# 1Bitsy.net
KiCad netlist of a schematic drawn in EAGLE
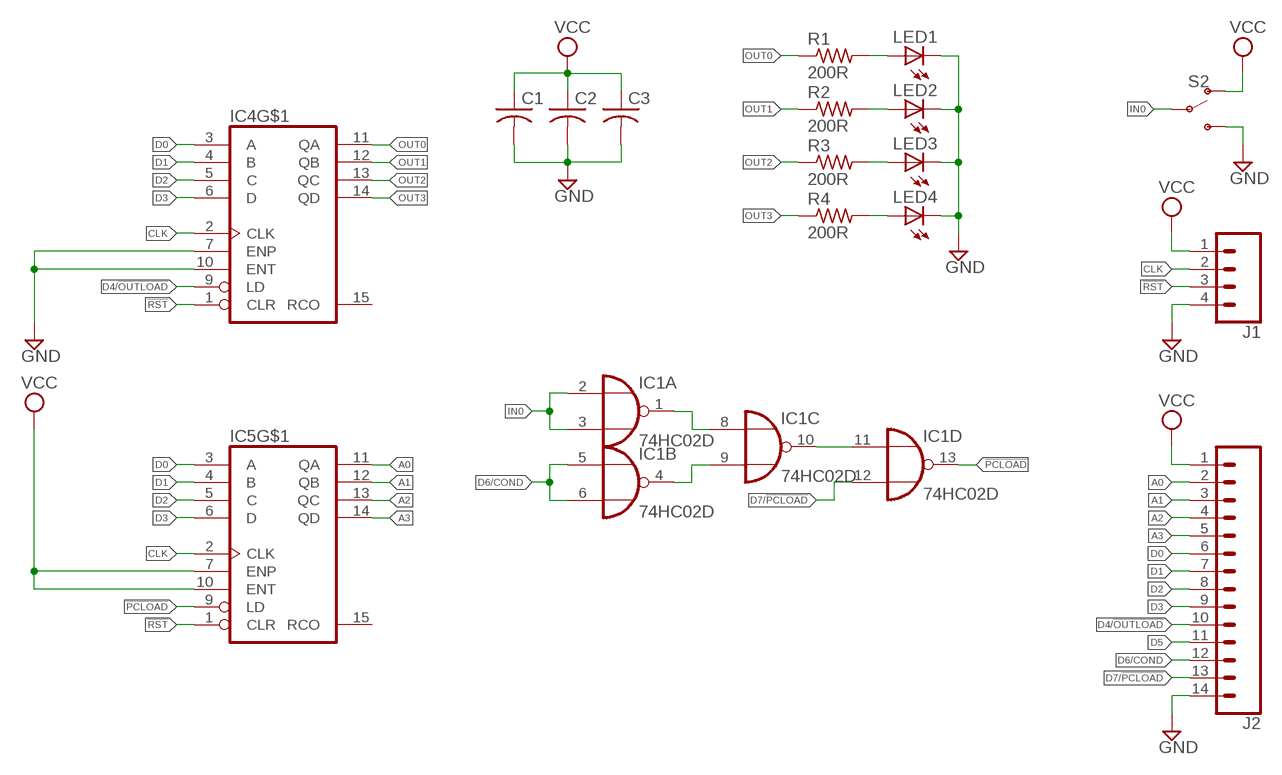
[diagram p0: schematic, sheet 1]

(export (version "E")
  (design (tool "Eeschema 10.0.6"))
  (components
    (comp (ref "C1")
      (value "C-USC0805")
      (footprint "eagle-import:C0805")
      (libsource (lib "eagle-import") (part "C-USC0805"))
    )
    (comp (ref "C2")
      (value "C-USC0805")
      (footprint "eagle-import:C0805")
      (libsource (lib "eagle-import") (part "C-USC0805"))
    )
    (comp (ref "C3")
      (value "C-USC0805")
      (footprint "eagle-import:C0805")
      (libsource (lib "eagle-import") (part "C-USC0805"))
    )
    (comp (ref "IC1")
      (value "74HC02D")
      (footprint "eagle-import:SO14")
      (libsource (lib "eagle-import") (part "7402DHC"))
    )
    (comp (ref "IC4")
      (value "74HC161")
      (footprint "eagle-import:SO16")
      (libsource (lib "eagle-import") (part "74161HC"))
    )
    (comp (ref "IC5")
      (value "74HC161")
      (footprint "eagle-import:SO16")
      (libsource (lib "eagle-import") (part "74161HC"))
    )
    (comp (ref "J1")
      (value "CONN_04")
      (footprint "eagle-import:1X04")
      (libsource (lib "eagle-import") (part "CONN_04"))
    )
    (comp (ref "J2")
      (value "CONN_14")
      (footprint "eagle-import:1X14")
      (libsource (lib "eagle-import") (part "CONN_14"))
    )
    (comp (ref "LED1")
      (value "LEDCHIP-LED0805")
      (footprint "eagle-import:CHIP-LED0805")
      (libsource (lib "eagle-import") (part "LEDCHIP-LED0805"))
    )
    (comp (ref "LED2")
      (value "LEDCHIP-LED0805")
      (footprint "eagle-import:CHIP-LED0805")
      (libsource (lib "eagle-import") (part "LEDCHIP-LED0805"))
    )
    (comp (ref "LED3")
      (value "LEDCHIP-LED0805")
      (footprint "eagle-import:CHIP-LED0805")
      (libsource (lib "eagle-import") (part "LEDCHIP-LED0805"))
    )
    (comp (ref "LED4")
      (value "LEDCHIP-LED0805")
      (footprint "eagle-import:CHIP-LED0805")
      (libsource (lib "eagle-import") (part "LEDCHIP-LED0805"))
    )
    (comp (ref "R1")
      (value "200R")
      (footprint "eagle-import:R0805")
      (libsource (lib "eagle-import") (part "R-US_R0805"))
    )
    (comp (ref "R2")
      (value "200R")
      (footprint "eagle-import:R0805")
      (libsource (lib "eagle-import") (part "R-US_R0805"))
    )
    (comp (ref "R3")
      (value "200R")
      (footprint "eagle-import:R0805")
      (libsource (lib "eagle-import") (part "R-US_R0805"))
    )
    (comp (ref "R4")
      (value "200R")
      (footprint "eagle-import:R0805")
      (libsource (lib "eagle-import") (part "R-US_R0805"))
    )
    (comp (ref "S2")
      (value "SWITCH-SPDT-SMD-RIGHT-ANGLE")
      (footprint "eagle-import:SWITCH_SPST_SMD_A")
      (libsource (lib "eagle-import") (part "SWITCH-SPDT-SMD-RIGHT-ANGLE"))
    )
  )
  (nets
    (net (code "1") (name "/D4{slash}~{OUTLOAD}") (class "Default")
      (node (ref "IC4") (pin "9") (pinfunction "LD_9") (pintype "input"))
      (node (ref "J2") (pin "10") (pinfunction "10_10") (pintype "passive"))
    )
    (net (code "2") (name "/D7{slash}~{PCLOAD}") (class "Default")
      (node (ref "IC1") (pin "12") (pinfunction "I1_12") (pintype "input"))
      (node (ref "J2") (pin "13") (pinfunction "13_13") (pintype "passive"))
    )
    (net (code "3") (name "/~{PCLOAD}") (class "Default")
      (node (ref "IC1") (pin "13") (pinfunction "O_13") (pintype "output"))
      (node (ref "IC5") (pin "9") (pinfunction "LD_9") (pintype "input"))
    )
    (net (code "4") (name "/~{RST}") (class "Default")
      (node (ref "IC4") (pin "1") (pinfunction "CLR_1") (pintype "input"))
      (node (ref "IC5") (pin "1") (pinfunction "CLR_1") (pintype "input"))
      (node (ref "J1") (pin "3") (pinfunction "3_3") (pintype "passive"))
    )
    (net (code "5") (name "A0") (class "Default")
      (node (ref "IC5") (pin "11") (pinfunction "QA_11") (pintype "output"))
      (node (ref "J2") (pin "2") (pinfunction "2_2") (pintype "passive"))
    )
    (net (code "6") (name "A1") (class "Default")
      (node (ref "IC5") (pin "12") (pinfunction "QB_12") (pintype "output"))
      (node (ref "J2") (pin "3") (pinfunction "3_3") (pintype "passive"))
    )
    (net (code "7") (name "A2") (class "Default")
      (node (ref "IC5") (pin "13") (pinfunction "QC_13") (pintype "output"))
      (node (ref "J2") (pin "4") (pinfunction "4_4") (pintype "passive"))
    )
    (net (code "8") (name "A3") (class "Default")
      (node (ref "IC5") (pin "14") (pinfunction "QD_14") (pintype "output"))
      (node (ref "J2") (pin "5") (pinfunction "5_5") (pintype "passive"))
    )
    (net (code "9") (name "CLK") (class "Default")
      (node (ref "IC4") (pin "2") (pinfunction "CLK_2") (pintype "input"))
      (node (ref "IC5") (pin "2") (pinfunction "CLK_2") (pintype "input"))
      (node (ref "J1") (pin "2") (pinfunction "2_2") (pintype "passive"))
    )
    (net (code "10") (name "D0") (class "Default")
      (node (ref "IC4") (pin "3") (pinfunction "A_3") (pintype "input"))
      (node (ref "IC5") (pin "3") (pinfunction "A_3") (pintype "input"))
      (node (ref "J2") (pin "6") (pinfunction "6_6") (pintype "passive"))
    )
    (net (code "11") (name "D1") (class "Default")
      (node (ref "IC4") (pin "4") (pinfunction "B_4") (pintype "input"))
      (node (ref "IC5") (pin "4") (pinfunction "B_4") (pintype "input"))
      (node (ref "J2") (pin "7") (pinfunction "7_7") (pintype "passive"))
    )
    (net (code "12") (name "D2") (class "Default")
      (node (ref "IC4") (pin "5") (pinfunction "C_5") (pintype "input"))
      (node (ref "IC5") (pin "5") (pinfunction "C_5") (pintype "input"))
      (node (ref "J2") (pin "8") (pinfunction "8_8") (pintype "passive"))
    )
    (net (code "13") (name "D3") (class "Default")
      (node (ref "IC4") (pin "6") (pinfunction "D_6") (pintype "input"))
      (node (ref "IC5") (pin "6") (pinfunction "D_6") (pintype "input"))
      (node (ref "J2") (pin "9") (pinfunction "9_9") (pintype "passive"))
    )
    (net (code "14") (name "D5") (class "Default")
      (node (ref "J2") (pin "11") (pinfunction "11_11") (pintype "passive"))
    )
    (net (code "15") (name "D6{slash}COND") (class "Default")
      (node (ref "IC1") (pin "5") (pinfunction "I0_5") (pintype "input"))
      (node (ref "IC1") (pin "6") (pinfunction "I1_6") (pintype "input"))
      (node (ref "J2") (pin "12") (pinfunction "12_12") (pintype "passive"))
    )
    (net (code "16") (name "GND") (class "Default")
      (node (ref "C1") (pin "2") (pinfunction "2_2") (pintype "passive"))
      (node (ref "C2") (pin "2") (pinfunction "2_2") (pintype "passive"))
      (node (ref "C3") (pin "2") (pinfunction "2_2") (pintype "passive"))
      (node (ref "IC4") (pin "10") (pinfunction "ENT_10") (pintype "input"))
      (node (ref "IC4") (pin "7") (pinfunction "ENP_7") (pintype "input"))
      (node (ref "J1") (pin "4") (pinfunction "4_4") (pintype "passive"))
      (node (ref "J2") (pin "14") (pinfunction "14_14") (pintype "passive"))
      (node (ref "LED1") (pin "C") (pinfunction "C_C") (pintype "passive"))
      (node (ref "LED2") (pin "C") (pinfunction "C_C") (pintype "passive"))
      (node (ref "LED3") (pin "C") (pinfunction "C_C") (pintype "passive"))
      (node (ref "LED4") (pin "C") (pinfunction "C_C") (pintype "passive"))
      (node (ref "S2") (pin "3") (pinfunction "S_3") (pintype "passive"))
    )
    (net (code "17") (name "IN0") (class "Default")
      (node (ref "IC1") (pin "2") (pinfunction "I0_2") (pintype "input"))
      (node (ref "IC1") (pin "3") (pinfunction "I1_3") (pintype "input"))
      (node (ref "S2") (pin "2") (pinfunction "P_2") (pintype "passive"))
    )
    (net (code "18") (name "Net-(IC1A-O)") (class "Default")
      (node (ref "IC1") (pin "1") (pinfunction "O_1") (pintype "output"))
      (node (ref "IC1") (pin "8") (pinfunction "I0_8") (pintype "input"))
    )
    (net (code "19") (name "Net-(IC1B-O)") (class "Default")
      (node (ref "IC1") (pin "4") (pinfunction "O_4") (pintype "output"))
      (node (ref "IC1") (pin "9") (pinfunction "I1_9") (pintype "input"))
    )
    (net (code "20") (name "Net-(IC1C-O)") (class "Default")
      (node (ref "IC1") (pin "10") (pinfunction "O_10") (pintype "output"))
      (node (ref "IC1") (pin "11") (pinfunction "I0_11") (pintype "input"))
    )
    (net (code "21") (name "Net-(LED1-PadA)") (class "Default")
      (node (ref "LED1") (pin "A") (pinfunction "A_A") (pintype "passive"))
      (node (ref "R1") (pin "2") (pinfunction "2_2") (pintype "passive"))
    )
    (net (code "22") (name "Net-(LED2-PadA)") (class "Default")
      (node (ref "LED2") (pin "A") (pinfunction "A_A") (pintype "passive"))
      (node (ref "R2") (pin "2") (pinfunction "2_2") (pintype "passive"))
    )
    (net (code "23") (name "Net-(LED3-PadA)") (class "Default")
      (node (ref "LED3") (pin "A") (pinfunction "A_A") (pintype "passive"))
      (node (ref "R3") (pin "2") (pinfunction "2_2") (pintype "passive"))
    )
    (net (code "24") (name "Net-(LED4-PadA)") (class "Default")
      (node (ref "LED4") (pin "A") (pinfunction "A_A") (pintype "passive"))
      (node (ref "R4") (pin "2") (pinfunction "2_2") (pintype "passive"))
    )
    (net (code "25") (name "OUT0") (class "Default")
      (node (ref "IC4") (pin "11") (pinfunction "QA_11") (pintype "output"))
      (node (ref "R1") (pin "1") (pinfunction "1_1") (pintype "passive"))
    )
    (net (code "26") (name "OUT1") (class "Default")
      (node (ref "IC4") (pin "12") (pinfunction "QB_12") (pintype "output"))
      (node (ref "R2") (pin "1") (pinfunction "1_1") (pintype "passive"))
    )
    (net (code "27") (name "OUT2") (class "Default")
      (node (ref "IC4") (pin "13") (pinfunction "QC_13") (pintype "output"))
      (node (ref "R3") (pin "1") (pinfunction "1_1") (pintype "passive"))
    )
    (net (code "28") (name "OUT3") (class "Default")
      (node (ref "IC4") (pin "14") (pinfunction "QD_14") (pintype "output"))
      (node (ref "R4") (pin "1") (pinfunction "1_1") (pintype "passive"))
    )
    (net (code "29") (name "VCC") (class "Default")
      (node (ref "C1") (pin "1") (pinfunction "1_1") (pintype "passive"))
      (node (ref "C2") (pin "1") (pinfunction "1_1") (pintype "passive"))
      (node (ref "C3") (pin "1") (pinfunction "1_1") (pintype "passive"))
      (node (ref "IC5") (pin "10") (pinfunction "ENT_10") (pintype "input"))
      (node (ref "IC5") (pin "7") (pinfunction "ENP_7") (pintype "input"))
      (node (ref "J1") (pin "1") (pinfunction "1_1") (pintype "passive"))
      (node (ref "J2") (pin "1") (pinfunction "1_1") (pintype "passive"))
      (node (ref "S2") (pin "1") (pinfunction "O_1") (pintype "passive"))
    )
    (net (code "30") (name "unconnected-(IC4A-RCO-Pad15)") (class "Default")
      (node (ref "IC4") (pin "15") (pinfunction "RCO_15") (pintype "output"))
    )
    (net (code "31") (name "unconnected-(IC5A-RCO-Pad15)") (class "Default")
      (node (ref "IC5") (pin "15") (pinfunction "RCO_15") (pintype "output"))
    )
  )
)
